# Blinky.net
KiCad netlist of a schematic drawn in EAGLE
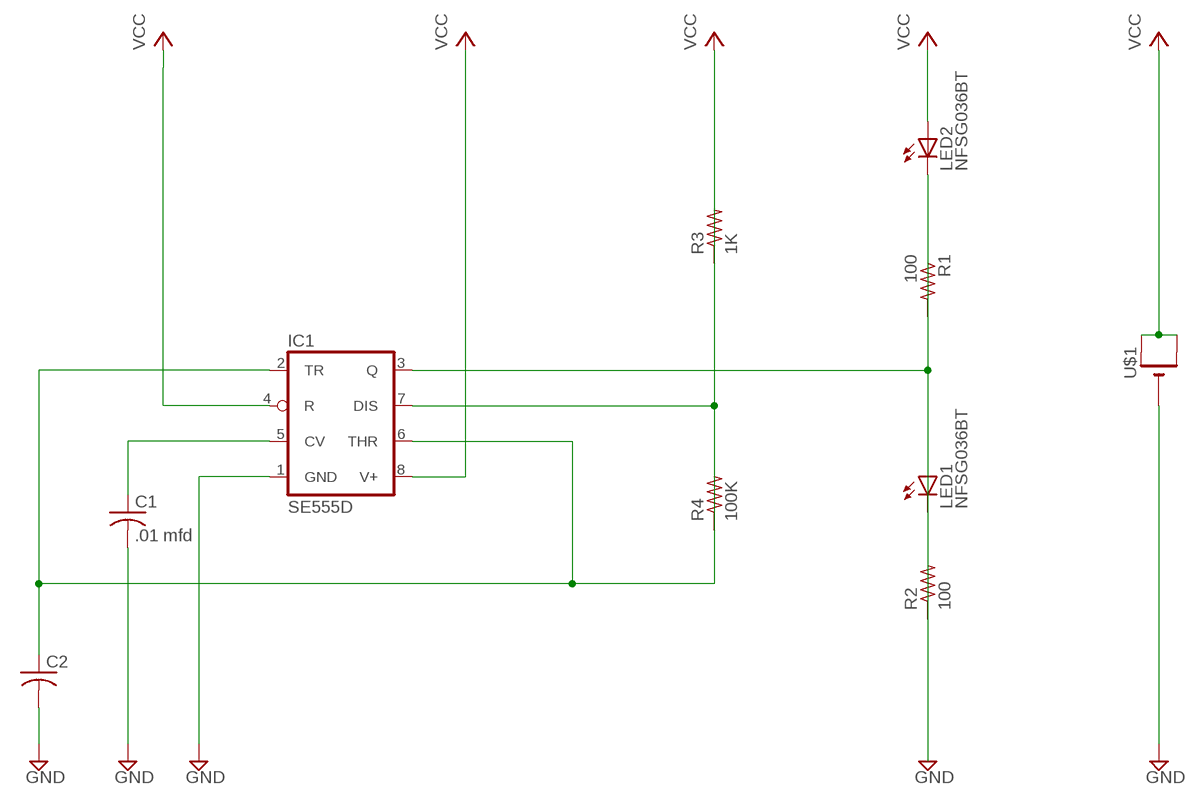
[diagram p0: schematic, sheet 1]

(export (version "E")
  (design (tool "Eeschema 10.0.6"))
  (components
    (comp (ref "C1")
      (value ".01 mfd")
      (footprint "eagle-import:C0805")
      (libsource (lib "eagle-import") (part "C-USC0805"))
    )
    (comp (ref "C2")
      (value "C-USC0805")
      (footprint "eagle-import:C0805")
      (libsource (lib "eagle-import") (part "C-USC0805"))
    )
    (comp (ref "IC1")
      (value "SE555D")
      (footprint "eagle-import:SO08")
      (libsource (lib "eagle-import") (part "555DSE"))
    )
    (comp (ref "LED1")
      (value "NFSG036BT")
      (footprint "eagle-import:NFSG036BT")
      (libsource (lib "eagle-import") (part "NFSG036BT"))
    )
    (comp (ref "LED2")
      (value "NFSG036BT")
      (footprint "eagle-import:NFSG036BT")
      (libsource (lib "eagle-import") (part "NFSG036BT"))
    )
    (comp (ref "R1")
      (value "100")
      (footprint "eagle-import:M0805")
      (libsource (lib "eagle-import") (part "R-US_M0805"))
    )
    (comp (ref "R2")
      (value "100")
      (footprint "eagle-import:M0805")
      (libsource (lib "eagle-import") (part "R-US_M0805"))
    )
    (comp (ref "R3")
      (value "1K")
      (footprint "eagle-import:M0805")
      (libsource (lib "eagle-import") (part "R-US_M0805"))
    )
    (comp (ref "R4")
      (value "100K")
      (footprint "eagle-import:M0805")
      (libsource (lib "eagle-import") (part "R-US_M0805"))
    )
    (comp (ref "U$1")
      (value "CR1220THM")
      (footprint "eagle-import:CR1220-THM")
      (libsource (lib "eagle-import") (part "CR1220THM"))
    )
  )
  (nets
    (net (code "1") (name "GND") (class "Default")
      (node (ref "C1") (pin "2") (pinfunction "2_2") (pintype "passive"))
      (node (ref "C2") (pin "2") (pinfunction "2_2") (pintype "passive"))
      (node (ref "IC1") (pin "1") (pinfunction "GND_1") (pintype "power_in"))
      (node (ref "IC1") (pin "3") (pinfunction "Q_3") (pintype "output"))
      (node (ref "LED2") (pin "C") (pinfunction "C_C") (pintype "passive"))
      (node (ref "R2") (pin "1") (pinfunction "1_1") (pintype "passive"))
      (node (ref "U$1") (pin "-") (pinfunction "-_-") (pintype "passive"))
    )
    (net (code "2") (name "Net-(IC1-CV)") (class "Default")
      (node (ref "C1") (pin "1") (pinfunction "1_1") (pintype "passive"))
      (node (ref "IC1") (pin "5") (pinfunction "CV_5") (pintype "input"))
    )
    (net (code "3") (name "VCC") (class "Default")
      (node (ref "C2") (pin "1") (pinfunction "1_1") (pintype "passive"))
      (node (ref "IC1") (pin "2") (pinfunction "TR_2") (pintype "input"))
      (node (ref "IC1") (pin "4") (pinfunction "R_4") (pintype "input"))
      (node (ref "IC1") (pin "6") (pinfunction "THR_6") (pintype "input"))
      (node (ref "IC1") (pin "7") (pinfunction "DIS_7") (pintype "input"))
      (node (ref "IC1") (pin "8") (pinfunction "V+_8") (pintype "power_in"))
      (node (ref "LED2") (pin "A") (pinfunction "A_A") (pintype "passive"))
      (node (ref "U$1") (pin "+1") (pinfunction "+_+1") (pintype "passive"))
      (node (ref "U$1") (pin "+2") (pinfunction "+1_+2") (pintype "passive"))
    )
    (net (code "4") (name "unconnected-(LED1-PadA)") (class "Default")
      (node (ref "LED1") (pin "A") (pinfunction "A_A") (pintype "passive"))
    )
    (net (code "5") (name "unconnected-(LED1-PadC)") (class "Default")
      (node (ref "LED1") (pin "C") (pinfunction "C_C") (pintype "passive"))
    )
    (net (code "6") (name "unconnected-(R1-Pad1)") (class "Default")
      (node (ref "R1") (pin "1") (pinfunction "1_1") (pintype "passive"))
    )
    (net (code "7") (name "unconnected-(R1-Pad2)") (class "Default")
      (node (ref "R1") (pin "2") (pinfunction "2_2") (pintype "passive"))
    )
    (net (code "8") (name "unconnected-(R2-Pad2)") (class "Default")
      (node (ref "R2") (pin "2") (pinfunction "2_2") (pintype "passive"))
    )
    (net (code "9") (name "unconnected-(R3-Pad1)") (class "Default")
      (node (ref "R3") (pin "1") (pinfunction "1_1") (pintype "passive"))
    )
    (net (code "10") (name "unconnected-(R3-Pad2)") (class "Default")
      (node (ref "R3") (pin "2") (pinfunction "2_2") (pintype "passive"))
    )
    (net (code "11") (name "unconnected-(R4-Pad1)") (class "Default")
      (node (ref "R4") (pin "1") (pinfunction "1_1") (pintype "passive"))
    )
    (net (code "12") (name "unconnected-(R4-Pad2)") (class "Default")
      (node (ref "R4") (pin "2") (pinfunction "2_2") (pintype "passive"))
    )
  )
)
